# pendulum_connector_board.net
KiCad netlist of a schematic drawn in EAGLE
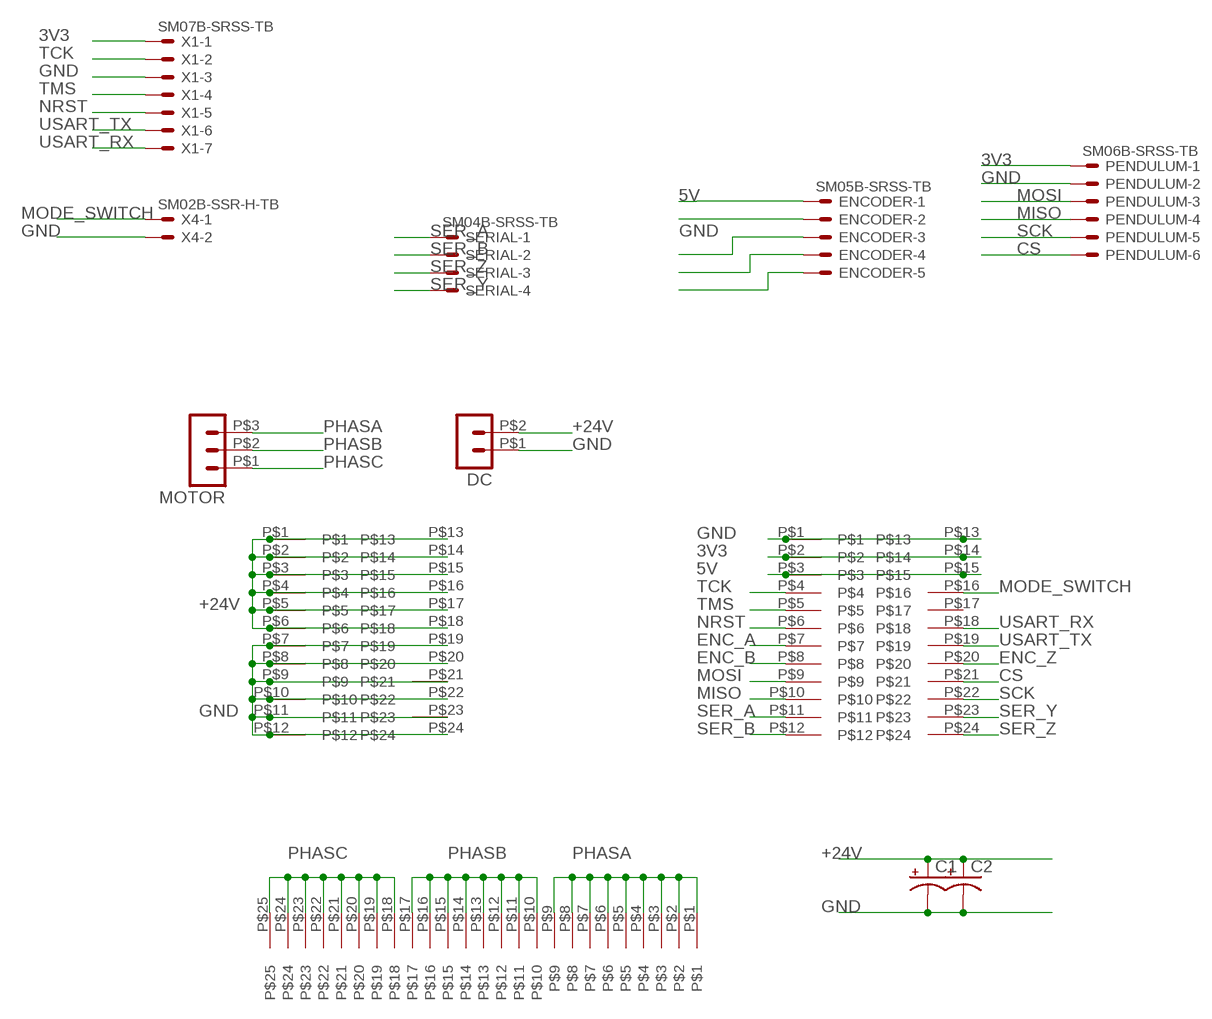
[diagram p0: schematic, sheet 1]

(export (version "E")
  (design (tool "Eeschema 10.0.6"))
  (components
    (comp (ref "C1")
      (value "CPOL-USE2.5-6")
      (footprint "eagle-import:E2,5-6")
      (libsource (lib "eagle-import") (part "CPOL-USE2.5-6"))
    )
    (comp (ref "C2")
      (value "CPOL-USE2.5-6")
      (footprint "eagle-import:E2,5-6")
      (libsource (lib "eagle-import") (part "CPOL-USE2.5-6"))
    )
    (comp (ref "DC")
      (value "HEADER_POS2_43650-0200")
      (footprint "eagle-import:43650-0200")
      (libsource (lib "eagle-import") (part "HEADER_POS2_?43650-0200"))
    )
    (comp (ref "ENCODER")
      (value "SM05B-SRSS-TB")
      (footprint "eagle-import:SM05B-SRSS-TB")
      (libsource (lib "eagle-import") (part "?M05B-SRSS-TBS"))
    )
    (comp (ref "MOTOR")
      (value "HEADER_POS3_43650-0300")
      (footprint "eagle-import:43650-0300")
      (libsource (lib "eagle-import") (part "HEADER_POS3_?43650-0300"))
    )
    (comp (ref "PENDULUM")
      (value "SM06B-SRSS-TB")
      (footprint "eagle-import:SM06B-SRSS-TB")
      (libsource (lib "eagle-import") (part "?M06B-SRSS-TBS"))
    )
    (comp (ref "SERIAL")
      (value "SM04B-SRSS-TB")
      (footprint "eagle-import:SM04B-SRSS-TB")
      (libsource (lib "eagle-import") (part "?M04B-SRSS-TBS"))
    )
    (comp (ref "U$2")
      (value "HEADER_2X12")
      (footprint "eagle-import:2X12X.05")
      (libsource (lib "eagle-import") (part "HEADER_2X12"))
    )
    (comp (ref "U$4")
      (value "HEADER_1X25")
      (footprint "eagle-import:1X25X.05")
      (libsource (lib "eagle-import") (part "HEADER_1X25"))
    )
    (comp (ref "U$5")
      (value "HEADER_2X12")
      (footprint "eagle-import:2X12X.05")
      (libsource (lib "eagle-import") (part "HEADER_2X12"))
    )
    (comp (ref "X1")
      (value "SM07B-SRSS-TB")
      (footprint "eagle-import:SM07B-SRSS-TB")
      (libsource (lib "eagle-import") (part "?M07B-SRSS-TBS"))
    )
    (comp (ref "X4")
      (value "SM02B-SSR-H-TB")
      (footprint "eagle-import:SM02B-SSR-H-TB")
      (libsource (lib "eagle-import") (part "SM02B-SSR-H-TB"))
    )
  )
  (nets
    (net (code "1") (name "/+24V") (class "Default")
      (node (ref "C1") (pin "+") (pinfunction "+_+") (pintype "passive"))
      (node (ref "C2") (pin "+") (pinfunction "+_+") (pintype "passive"))
      (node (ref "DC") (pin "P$2") (pinfunction "2_P$2") (pintype "passive"))
      (node (ref "U$5") (pin "P$1") (pinfunction "P$1_P$1") (pintype "bidirectional"))
      (node (ref "U$5") (pin "P$13") (pinfunction "P$13_P$13") (pintype "bidirectional"))
      (node (ref "U$5") (pin "P$14") (pinfunction "P$14_P$14") (pintype "bidirectional"))
      (node (ref "U$5") (pin "P$15") (pinfunction "P$15_P$15") (pintype "bidirectional"))
      (node (ref "U$5") (pin "P$16") (pinfunction "P$16_P$16") (pintype "bidirectional"))
      (node (ref "U$5") (pin "P$17") (pinfunction "P$17_P$17") (pintype "bidirectional"))
      (node (ref "U$5") (pin "P$18") (pinfunction "P$18_P$18") (pintype "bidirectional"))
      (node (ref "U$5") (pin "P$2") (pinfunction "P$2_P$2") (pintype "bidirectional"))
      (node (ref "U$5") (pin "P$3") (pinfunction "P$3_P$3") (pintype "bidirectional"))
      (node (ref "U$5") (pin "P$4") (pinfunction "P$4_P$4") (pintype "bidirectional"))
      (node (ref "U$5") (pin "P$5") (pinfunction "P$5_P$5") (pintype "bidirectional"))
      (node (ref "U$5") (pin "P$6") (pinfunction "P$6_P$6") (pintype "bidirectional"))
    )
    (net (code "2") (name "/3V3") (class "Default")
      (node (ref "PENDULUM") (pin "1") (pinfunction "S_1") (pintype "passive"))
      (node (ref "U$2") (pin "P$14") (pinfunction "P$14_P$14") (pintype "bidirectional"))
      (node (ref "U$2") (pin "P$2") (pinfunction "P$2_P$2") (pintype "bidirectional"))
      (node (ref "X1") (pin "1") (pinfunction "S_1") (pintype "passive"))
    )
    (net (code "3") (name "/5V") (class "Default")
      (node (ref "ENCODER") (pin "1") (pinfunction "S_1") (pintype "passive"))
      (node (ref "U$2") (pin "P$15") (pinfunction "P$15_P$15") (pintype "bidirectional"))
      (node (ref "U$2") (pin "P$3") (pinfunction "P$3_P$3") (pintype "bidirectional"))
    )
    (net (code "4") (name "/CS") (class "Default")
      (node (ref "PENDULUM") (pin "6") (pinfunction "S_6") (pintype "passive"))
      (node (ref "U$2") (pin "P$21") (pinfunction "P$21_P$21") (pintype "bidirectional"))
    )
    (net (code "5") (name "/ENC_A") (class "Default")
      (node (ref "ENCODER") (pin "3") (pinfunction "S_3") (pintype "passive"))
      (node (ref "U$2") (pin "P$7") (pinfunction "P$7_P$7") (pintype "bidirectional"))
    )
    (net (code "6") (name "/ENC_B") (class "Default")
      (node (ref "ENCODER") (pin "4") (pinfunction "S_4") (pintype "passive"))
      (node (ref "U$2") (pin "P$8") (pinfunction "P$8_P$8") (pintype "bidirectional"))
    )
    (net (code "7") (name "/ENC_Z") (class "Default")
      (node (ref "ENCODER") (pin "5") (pinfunction "S_5") (pintype "passive"))
      (node (ref "U$2") (pin "P$20") (pinfunction "P$20_P$20") (pintype "bidirectional"))
    )
    (net (code "8") (name "/GND") (class "Default")
      (node (ref "C1") (pin "-") (pinfunction "-_-") (pintype "passive"))
      (node (ref "C2") (pin "-") (pinfunction "-_-") (pintype "passive"))
      (node (ref "DC") (pin "P$1") (pinfunction "1_P$1") (pintype "passive"))
      (node (ref "ENCODER") (pin "2") (pinfunction "S_2") (pintype "passive"))
      (node (ref "PENDULUM") (pin "2") (pinfunction "S_2") (pintype "passive"))
      (node (ref "U$2") (pin "P$1") (pinfunction "P$1_P$1") (pintype "bidirectional"))
      (node (ref "U$2") (pin "P$13") (pinfunction "P$13_P$13") (pintype "bidirectional"))
      (node (ref "U$5") (pin "P$10") (pinfunction "P$10_P$10") (pintype "bidirectional"))
      (node (ref "U$5") (pin "P$11") (pinfunction "P$11_P$11") (pintype "bidirectional"))
      (node (ref "U$5") (pin "P$12") (pinfunction "P$12_P$12") (pintype "bidirectional"))
      (node (ref "U$5") (pin "P$19") (pinfunction "P$19_P$19") (pintype "bidirectional"))
      (node (ref "U$5") (pin "P$20") (pinfunction "P$20_P$20") (pintype "bidirectional"))
      (node (ref "U$5") (pin "P$21") (pinfunction "P$21_P$21") (pintype "bidirectional"))
      (node (ref "U$5") (pin "P$22") (pinfunction "P$22_P$22") (pintype "bidirectional"))
      (node (ref "U$5") (pin "P$23") (pinfunction "P$23_P$23") (pintype "bidirectional"))
      (node (ref "U$5") (pin "P$24") (pinfunction "P$24_P$24") (pintype "bidirectional"))
      (node (ref "U$5") (pin "P$7") (pinfunction "P$7_P$7") (pintype "bidirectional"))
      (node (ref "U$5") (pin "P$8") (pinfunction "P$8_P$8") (pintype "bidirectional"))
      (node (ref "U$5") (pin "P$9") (pinfunction "P$9_P$9") (pintype "bidirectional"))
      (node (ref "X1") (pin "3") (pinfunction "S_3") (pintype "passive"))
      (node (ref "X4") (pin "2") (pinfunction "S_2") (pintype "passive"))
    )
    (net (code "9") (name "/MISO") (class "Default")
      (node (ref "PENDULUM") (pin "4") (pinfunction "S_4") (pintype "passive"))
      (node (ref "U$2") (pin "P$10") (pinfunction "P$10_P$10") (pintype "bidirectional"))
    )
    (net (code "10") (name "/MODE_SWITCH") (class "Default")
      (node (ref "U$2") (pin "P$16") (pinfunction "P$16_P$16") (pintype "bidirectional"))
      (node (ref "X4") (pin "1") (pinfunction "S_1") (pintype "passive"))
    )
    (net (code "11") (name "/MOSI") (class "Default")
      (node (ref "PENDULUM") (pin "3") (pinfunction "S_3") (pintype "passive"))
      (node (ref "U$2") (pin "P$9") (pinfunction "P$9_P$9") (pintype "bidirectional"))
    )
    (net (code "12") (name "/NRST") (class "Default")
      (node (ref "U$2") (pin "P$6") (pinfunction "P$6_P$6") (pintype "bidirectional"))
      (node (ref "X1") (pin "5") (pinfunction "S_5") (pintype "passive"))
    )
    (net (code "13") (name "/PHASA") (class "Default")
      (node (ref "MOTOR") (pin "P$3") (pinfunction "3_P$3") (pintype "passive"))
      (node (ref "U$4") (pin "P$1") (pinfunction "P$1_P$1") (pintype "bidirectional"))
      (node (ref "U$4") (pin "P$2") (pinfunction "P$2_P$2") (pintype "bidirectional"))
      (node (ref "U$4") (pin "P$3") (pinfunction "P$3_P$3") (pintype "bidirectional"))
      (node (ref "U$4") (pin "P$4") (pinfunction "P$4_P$4") (pintype "bidirectional"))
      (node (ref "U$4") (pin "P$5") (pinfunction "P$5_P$5") (pintype "bidirectional"))
      (node (ref "U$4") (pin "P$6") (pinfunction "P$6_P$6") (pintype "bidirectional"))
      (node (ref "U$4") (pin "P$7") (pinfunction "P$7_P$7") (pintype "bidirectional"))
      (node (ref "U$4") (pin "P$8") (pinfunction "P$8_P$8") (pintype "bidirectional"))
      (node (ref "U$4") (pin "P$9") (pinfunction "P$9_P$9") (pintype "bidirectional"))
    )
    (net (code "14") (name "/PHASB") (class "Default")
      (node (ref "MOTOR") (pin "P$2") (pinfunction "2_P$2") (pintype "passive"))
      (node (ref "U$4") (pin "P$10") (pinfunction "P$10_P$10") (pintype "bidirectional"))
      (node (ref "U$4") (pin "P$11") (pinfunction "P$11_P$11") (pintype "bidirectional"))
      (node (ref "U$4") (pin "P$12") (pinfunction "P$12_P$12") (pintype "bidirectional"))
      (node (ref "U$4") (pin "P$13") (pinfunction "P$13_P$13") (pintype "bidirectional"))
      (node (ref "U$4") (pin "P$14") (pinfunction "P$14_P$14") (pintype "bidirectional"))
      (node (ref "U$4") (pin "P$15") (pinfunction "P$15_P$15") (pintype "bidirectional"))
      (node (ref "U$4") (pin "P$16") (pinfunction "P$16_P$16") (pintype "bidirectional"))
      (node (ref "U$4") (pin "P$17") (pinfunction "P$17_P$17") (pintype "bidirectional"))
    )
    (net (code "15") (name "/PHASC") (class "Default")
      (node (ref "MOTOR") (pin "P$1") (pinfunction "1_P$1") (pintype "passive"))
      (node (ref "U$4") (pin "P$18") (pinfunction "P$18_P$18") (pintype "bidirectional"))
      (node (ref "U$4") (pin "P$19") (pinfunction "P$19_P$19") (pintype "bidirectional"))
      (node (ref "U$4") (pin "P$20") (pinfunction "P$20_P$20") (pintype "bidirectional"))
      (node (ref "U$4") (pin "P$21") (pinfunction "P$21_P$21") (pintype "bidirectional"))
      (node (ref "U$4") (pin "P$22") (pinfunction "P$22_P$22") (pintype "bidirectional"))
      (node (ref "U$4") (pin "P$23") (pinfunction "P$23_P$23") (pintype "bidirectional"))
      (node (ref "U$4") (pin "P$24") (pinfunction "P$24_P$24") (pintype "bidirectional"))
      (node (ref "U$4") (pin "P$25") (pinfunction "P$25_P$25") (pintype "bidirectional"))
    )
    (net (code "16") (name "/SCK") (class "Default")
      (node (ref "PENDULUM") (pin "5") (pinfunction "S_5") (pintype "passive"))
      (node (ref "U$2") (pin "P$22") (pinfunction "P$22_P$22") (pintype "bidirectional"))
    )
    (net (code "17") (name "/SER_A") (class "Default")
      (node (ref "SERIAL") (pin "1") (pinfunction "S_1") (pintype "passive"))
      (node (ref "U$2") (pin "P$11") (pinfunction "P$11_P$11") (pintype "bidirectional"))
    )
    (net (code "18") (name "/SER_B") (class "Default")
      (node (ref "SERIAL") (pin "2") (pinfunction "S_2") (pintype "passive"))
      (node (ref "U$2") (pin "P$12") (pinfunction "P$12_P$12") (pintype "bidirectional"))
    )
    (net (code "19") (name "/SER_Y") (class "Default")
      (node (ref "SERIAL") (pin "4") (pinfunction "S_4") (pintype "passive"))
      (node (ref "U$2") (pin "P$23") (pinfunction "P$23_P$23") (pintype "bidirectional"))
    )
    (net (code "20") (name "/SER_Z") (class "Default")
      (node (ref "SERIAL") (pin "3") (pinfunction "S_3") (pintype "passive"))
      (node (ref "U$2") (pin "P$24") (pinfunction "P$24_P$24") (pintype "bidirectional"))
    )
    (net (code "21") (name "/TCK") (class "Default")
      (node (ref "U$2") (pin "P$4") (pinfunction "P$4_P$4") (pintype "bidirectional"))
      (node (ref "X1") (pin "2") (pinfunction "S_2") (pintype "passive"))
    )
    (net (code "22") (name "/TMS") (class "Default")
      (node (ref "U$2") (pin "P$5") (pinfunction "P$5_P$5") (pintype "bidirectional"))
      (node (ref "X1") (pin "4") (pinfunction "S_4") (pintype "passive"))
    )
    (net (code "23") (name "/USART_RX") (class "Default")
      (node (ref "U$2") (pin "P$18") (pinfunction "P$18_P$18") (pintype "bidirectional"))
      (node (ref "X1") (pin "7") (pinfunction "S_7") (pintype "passive"))
    )
    (net (code "24") (name "/USART_TX") (class "Default")
      (node (ref "U$2") (pin "P$19") (pinfunction "P$19_P$19") (pintype "bidirectional"))
      (node (ref "X1") (pin "6") (pinfunction "S_6") (pintype "passive"))
    )
    (net (code "25") (name "unconnected-(U$2-PadP$17)") (class "Default")
      (node (ref "U$2") (pin "P$17") (pinfunction "P$17_P$17") (pintype "bidirectional"))
    )
  )
)
